# MCU.net
KiCad netlist of a schematic drawn in Altium Designer
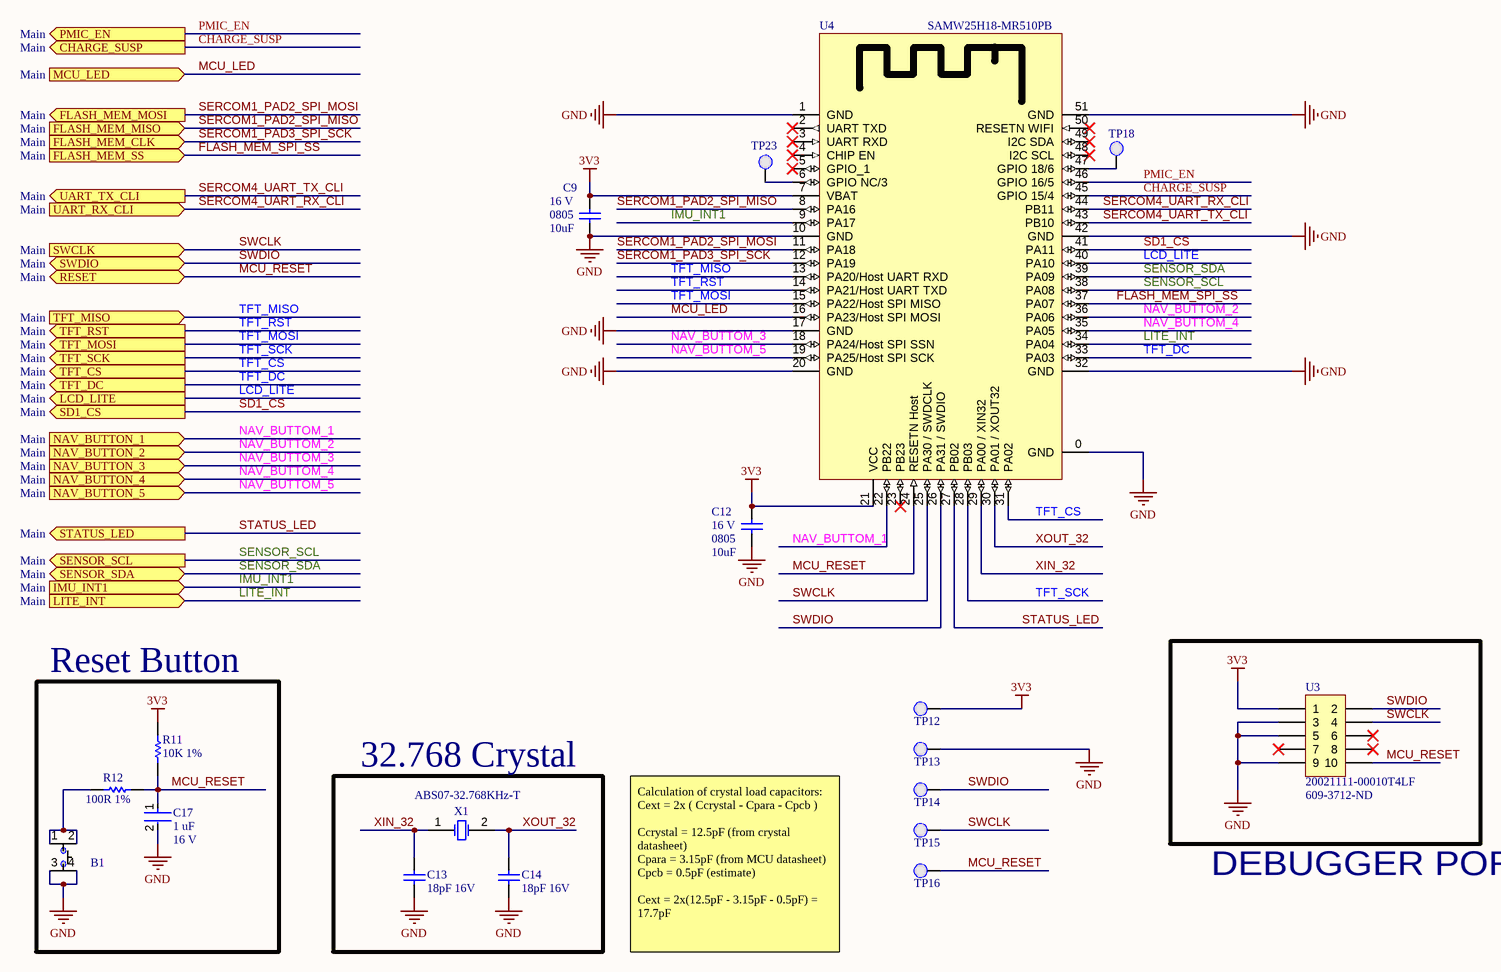
[diagram p0: MCU.SchDoc]

(export (version "E")
  (design (tool "Eeschema 10.0.6"))
  (components
    (comp (ref "B1")
      (value "PTS810 SJK 250 SMTR LFS")
      (footprint "PTS810 SJK 250 SMTR LFS")
      (description "SWITCH TACTILE SPST-NO 0.05A 16V Tactile Switch SPST-NO Top Actuated Surface Mount")
      (fields
        (field (name "MANUFACTURER") "ITT /  C&K Components")
        (field (name "MANUFACTURER PART NUMBER") "PTS810SJK250SMTRLFS")
      )
      (libsource (lib "Schematics") (part "PTS810 SJK 250 SMTR LFS"))
    )
    (comp (ref "C9")
      (value "10uF")
      (footprint "CAPC0805(2012)145_N")
      (description "CAP 10uF 16V ±10% 0805 (2012 Metric) Thickness 1.45mm SMD")
      (fields
        (field (name "RATED VOLTAGE") "16 V")
        (field (name "CASE-EIA") "0805")
        (field (name "TOLERANCE") "Â±10%")
        (field (name "MANUFACTURER PART NUMBER") "CC0805KKX7R7BB106")
      )
      (libsource (lib "ProtoWatch_Compiled") (part "CMP-1036-04927-1"))
    )
    (comp (ref "C12")
      (value "10uF")
      (footprint "CAPC0805(2012)145_N")
      (description "CAP 10uF 16V ±10% 0805 (2012 Metric) Thickness 1.45mm SMD")
      (fields
        (field (name "RATED VOLTAGE") "16 V")
        (field (name "CASE-EIA") "0805")
        (field (name "TOLERANCE") "Â±10%")
        (field (name "MANUFACTURER PART NUMBER") "CC0805KKX7R7BB106")
      )
      (libsource (lib "ProtoWatch_Compiled") (part "CMP-1036-04927-1"))
    )
    (comp (ref "C13")
      (value "18pF 16V")
      (footprint "CAPC0603(1608)100_N")
      (description "CAP 18pF 16V ±5% 0603 (1608 Metric) Thickness 1mm SMD")
      (fields (field (name "TOLERANCE") "Â±5%"))
      (libsource (lib "Altium Content Vault") (part "CAP"))
    )
    (comp (ref "C14")
      (value "18pF 16V")
      (footprint "CAPC0603(1608)100_N")
      (description "CAP 18pF 16V ±5% 0603 (1608 Metric) Thickness 1mm SMD")
      (fields (field (name "TOLERANCE") "Â±5%"))
      (libsource (lib "Altium Content Vault") (part "CAP"))
    )
    (comp (ref "C17")
      (value "1 uF")
      (footprint "FP-CC0603-DA-MFG")
      (description "CAP CER 1UF 16V X7R 0603")
      (fields
        (field (name "TOLERANCE") "0.1")
        (field (name "MANUFACTURER") "YAGEO")
        (field (name "VOLTAGE") "16 V")
      )
      (libsource (lib "Altium Content Vault") (part "11868f565c42a9108669ba33697ecf6"))
    )
    (comp (ref "R11")
      (value "10K 1%")
      (footprint "RESC0603(1608)_N")
      (description "10K 0.1W 1% 0603 (1608 Metric)  SMD")
      (fields (field (name "POWER") "0.1 W") (field (name "TOLERANCE") "1 %"))
      (libsource (lib "Altium Content Vault") (part "RES"))
    )
    (comp (ref "R12")
      (value "100R 1%")
      (footprint "RESC0603(1608)_N")
      (description "100R 0.1W 1% 0603 (1608 Metric)  SMD")
      (fields (field (name "TOLERANCE") "1 %") (field (name "POWER") "0.1 W"))
      (libsource (lib "Altium Content Vault") (part "RES"))
    )
    (comp (ref "TP12")
      (value "0.1\" Pad")
      (footprint "PCBComponent")
      (libsource (lib "Components - 12.02.20 - 18.05") (part "0.1{dblquote} Pad-A.4"))
    )
    (comp (ref "TP13")
      (value "0.1\" Pad")
      (footprint "PCBComponent")
      (libsource (lib "Components - 12.02.20 - 18.05") (part "0.1{dblquote} Pad-A.4"))
    )
    (comp (ref "TP14")
      (value "0.1\" Pad")
      (footprint "PCBComponent")
      (libsource (lib "Components - 12.02.20 - 18.05") (part "0.1{dblquote} Pad-A.4"))
    )
    (comp (ref "TP15")
      (value "0.1\" Pad")
      (footprint "PCBComponent")
      (libsource (lib "Components - 12.02.20 - 18.05") (part "0.1{dblquote} Pad-A.4"))
    )
    (comp (ref "TP16")
      (value "0.1\" Pad")
      (footprint "PCBComponent")
      (libsource (lib "Components - 12.02.20 - 18.05") (part "0.1{dblquote} Pad-A.4"))
    )
    (comp (ref "TP18")
      (value "0.1\" Pad")
      (footprint "PCBComponent")
      (libsource (lib "Components - 12.02.20 - 18.05") (part "0.1{dblquote} Pad-A.4"))
    )
    (comp (ref "TP23")
      (value "0.1\" Pad")
      (footprint "PCBComponent")
      (libsource (lib "Components - 12.02.20 - 18.05") (part "0.1{dblquote} Pad-A.4"))
    )
    (comp (ref "U3")
      (value "20021111-00010T4LF")
      (footprint "20021111-00010T4LF")
      (description "CONN HEADER 10POS UNSHD VERT T/H")
      (fields
        (field (name "MANUFACTURER") "Amphenol / FCI")
        (field (name "SUPPLIER PART NUMBER 1") "609-3712-ND")
      )
      (libsource (lib "Schematics") (part "20021111-00010T4LF"))
    )
    (comp (ref "U4")
      (value "SAMW25H18-MR510PB")
      (footprint "SAMW25H18-MR510PB")
      (description "RF TXRX MODULE WIFI TRACE ANT")
      (fields
        (field (name "MANUFACTURER") "Atmel")
        (field (name "MANUFACTURER PART NUMBER") "ATSAMW25H18-MR510PB")
      )
      (libsource (lib "Schematics") (part "SAMW25H18-MR510PB"))
    )
    (comp (ref "X1")
      (value "ABS07-32.768KHz-T")
      (footprint "ABRA-ABS07-2_V")
      (description "Crystal, 32.768 kHz, 12.5 pF, -40 to 85 degC, SMD Low Profile 3.2 x 1.5 x 0.9 mm, Tape and Reel")
      (fields (field (name "MANUFACTURER") "Abracon"))
      (libsource (lib "Altium Content Vault") (part "ABRA-ABS07-2"))
    )
  )
  (nets
    (net (code "1") (name "/CHARGE_SUSP") (class "Default")
      (node (ref "U4") (pin "45") (pinfunction "GPIO_15/4_45") (pintype "bidirectional"))
    )
    (net (code "2") (name "/FLASH_MEM_SPI_SS") (class "Default")
      (node (ref "U4") (pin "37") (pinfunction "PA07_37") (pintype "bidirectional"))
    )
    (net (code "3") (name "/IMU_INT1") (class "Default")
      (node (ref "U4") (pin "9") (pinfunction "PA17_9") (pintype "bidirectional"))
    )
    (net (code "4") (name "/LCD_LITE") (class "Default")
      (node (ref "U4") (pin "40") (pinfunction "PA10_40") (pintype "bidirectional"))
    )
    (net (code "5") (name "/LITE_INT") (class "Default")
      (node (ref "U4") (pin "34") (pinfunction "PA04_34") (pintype "bidirectional"))
    )
    (net (code "6") (name "/MCU_LED") (class "Default")
      (node (ref "U4") (pin "16") (pinfunction "PA23/Host_SPI_MOSI_16") (pintype "bidirectional"))
    )
    (net (code "7") (name "/MCU_RESET") (class "Default")
      (node (ref "C17") (pin "1") (pinfunction "1_1") (pintype "passive"))
      (node (ref "R11") (pin "1") (pinfunction "1_1") (pintype "passive"))
      (node (ref "R12") (pin "2") (pinfunction "2_2") (pintype "passive"))
      (node (ref "TP16") (pin "1") (pinfunction "PAD_1") (pintype "passive"))
      (node (ref "U3") (pin "10") (pinfunction "10_10") (pintype "passive"))
      (node (ref "U4") (pin "24") (pinfunction "RESETN_Host_24") (pintype "input"))
    )
    (net (code "8") (name "/NAV_BUTTOM_1") (class "Default")
      (node (ref "U4") (pin "22") (pinfunction "PB22_22") (pintype "bidirectional"))
    )
    (net (code "9") (name "/NAV_BUTTOM_2") (class "Default")
      (node (ref "U4") (pin "36") (pinfunction "PA06_36") (pintype "bidirectional"))
    )
    (net (code "10") (name "/NAV_BUTTOM_3") (class "Default")
      (node (ref "U4") (pin "18") (pinfunction "PA24/Host_SPI_SSN_18") (pintype "bidirectional"))
    )
    (net (code "11") (name "/NAV_BUTTOM_4") (class "Default")
      (node (ref "U4") (pin "35") (pinfunction "PA05_35") (pintype "bidirectional"))
    )
    (net (code "12") (name "/NAV_BUTTOM_5") (class "Default")
      (node (ref "U4") (pin "19") (pinfunction "PA25/Host_SPI_SCK_19") (pintype "bidirectional"))
    )
    (net (code "13") (name "/PMIC_EN") (class "Default")
      (node (ref "U4") (pin "46") (pinfunction "GPIO_16/5_46") (pintype "bidirectional"))
    )
    (net (code "14") (name "/SD1_CS") (class "Default")
      (node (ref "U4") (pin "41") (pinfunction "PA11_41") (pintype "bidirectional"))
    )
    (net (code "15") (name "/SENSOR_SCL") (class "Default")
      (node (ref "U4") (pin "38") (pinfunction "PA08_38") (pintype "bidirectional"))
    )
    (net (code "16") (name "/SENSOR_SDA") (class "Default")
      (node (ref "U4") (pin "39") (pinfunction "PA09_39") (pintype "bidirectional"))
    )
    (net (code "17") (name "/SERCOM1_PAD2_SPI_MISO") (class "Default")
      (node (ref "U4") (pin "8") (pinfunction "PA16_8") (pintype "bidirectional"))
    )
    (net (code "18") (name "/SERCOM1_PAD2_SPI_MOSI") (class "Default")
      (node (ref "U4") (pin "11") (pinfunction "PA18_11") (pintype "bidirectional"))
    )
    (net (code "19") (name "/SERCOM1_PAD3_SPI_SCK") (class "Default")
      (node (ref "U4") (pin "12") (pinfunction "PA19_12") (pintype "bidirectional"))
    )
    (net (code "20") (name "/SERCOM4_UART_RX_CLI") (class "Default")
      (node (ref "U4") (pin "44") (pinfunction "PB11_44") (pintype "bidirectional"))
    )
    (net (code "21") (name "/SERCOM4_UART_TX_CLI") (class "Default")
      (node (ref "U4") (pin "43") (pinfunction "PB10_43") (pintype "bidirectional"))
    )
    (net (code "22") (name "/STATUS_LED") (class "Default")
      (node (ref "U4") (pin "27") (pinfunction "PB02_27") (pintype "bidirectional"))
    )
    (net (code "23") (name "/SWCLK") (class "Default")
      (node (ref "TP15") (pin "1") (pinfunction "PAD_1") (pintype "passive"))
      (node (ref "U3") (pin "4") (pinfunction "4_4") (pintype "passive"))
      (node (ref "U4") (pin "25") (pinfunction "PA30_/_SWDCLK_25") (pintype "bidirectional"))
    )
    (net (code "24") (name "/SWDIO") (class "Default")
      (node (ref "TP14") (pin "1") (pinfunction "PAD_1") (pintype "passive"))
      (node (ref "U3") (pin "2") (pinfunction "2_2") (pintype "passive"))
      (node (ref "U4") (pin "26") (pinfunction "PA31_/_SWDIO_26") (pintype "bidirectional"))
    )
    (net (code "25") (name "/TFT_CS") (class "Default")
      (node (ref "U4") (pin "31") (pinfunction "PA02_31") (pintype "bidirectional"))
    )
    (net (code "26") (name "/TFT_DC") (class "Default")
      (node (ref "U4") (pin "33") (pinfunction "PA03_33") (pintype "bidirectional"))
    )
    (net (code "27") (name "/TFT_MISO") (class "Default")
      (node (ref "U4") (pin "13") (pinfunction "PA20/Host_UART_RXD_13") (pintype "bidirectional"))
    )
    (net (code "28") (name "/TFT_MOSI") (class "Default")
      (node (ref "U4") (pin "15") (pinfunction "PA22/Host_SPI_MISO_15") (pintype "bidirectional"))
    )
    (net (code "29") (name "/TFT_RST") (class "Default")
      (node (ref "U4") (pin "14") (pinfunction "PA21/Host_UART_TXD_14") (pintype "bidirectional"))
    )
    (net (code "30") (name "/TFT_SCK") (class "Default")
      (node (ref "U4") (pin "28") (pinfunction "PB03_28") (pintype "bidirectional"))
    )
    (net (code "31") (name "/XIN_32") (class "Default")
      (node (ref "C13") (pin "2") (pinfunction "2_2") (pintype "passive"))
      (node (ref "U4") (pin "29") (pinfunction "PA00_/_XIN32_29") (pintype "bidirectional"))
      (node (ref "X1") (pin "1") (pinfunction "X1_1") (pintype "passive"))
    )
    (net (code "32") (name "/XOUT_32") (class "Default")
      (node (ref "C14") (pin "2") (pinfunction "2_2") (pintype "passive"))
      (node (ref "U4") (pin "30") (pinfunction "PA01_/_XOUT32_30") (pintype "bidirectional"))
      (node (ref "X1") (pin "2") (pinfunction "X2_2") (pintype "passive"))
    )
    (net (code "33") (name "3V3") (class "Default")
      (node (ref "C12") (pin "2") (pinfunction "2_2") (pintype "passive"))
      (node (ref "C9") (pin "2") (pinfunction "2_2") (pintype "passive"))
      (node (ref "R11") (pin "2") (pinfunction "2_2") (pintype "passive"))
      (node (ref "TP12") (pin "1") (pinfunction "PAD_1") (pintype "passive"))
      (node (ref "U3") (pin "1") (pinfunction "1_1") (pintype "passive"))
      (node (ref "U4") (pin "21") (pinfunction "VCC_21") (pintype "power_in"))
      (node (ref "U4") (pin "7") (pinfunction "VBAT_7") (pintype "power_in"))
    )
    (net (code "34") (name "GND") (class "Default")
      (node (ref "B1") (pin "3") (pinfunction "3_3") (pintype "power_in"))
      (node (ref "B1") (pin "4") (pinfunction "4_4") (pintype "power_in"))
      (node (ref "C12") (pin "1") (pinfunction "1_1") (pintype "passive"))
      (node (ref "C13") (pin "1") (pinfunction "1_1") (pintype "passive"))
      (node (ref "C14") (pin "1") (pinfunction "1_1") (pintype "passive"))
      (node (ref "C17") (pin "2") (pinfunction "2_2") (pintype "passive"))
      (node (ref "C9") (pin "1") (pinfunction "1_1") (pintype "passive"))
      (node (ref "TP13") (pin "1") (pinfunction "PAD_1") (pintype "passive"))
      (node (ref "U3") (pin "3") (pinfunction "3_3") (pintype "passive"))
      (node (ref "U3") (pin "5") (pinfunction "5_5") (pintype "passive"))
      (node (ref "U3") (pin "9") (pinfunction "9_9") (pintype "passive"))
      (node (ref "U4") (pin "0") (pinfunction "GND_0") (pintype "power_in"))
      (node (ref "U4") (pin "1") (pinfunction "GND_1") (pintype "power_in"))
      (node (ref "U4") (pin "10") (pinfunction "GND_10") (pintype "power_in"))
      (node (ref "U4") (pin "17") (pinfunction "GND_17") (pintype "power_in"))
      (node (ref "U4") (pin "20") (pinfunction "GND_20") (pintype "power_in"))
      (node (ref "U4") (pin "32") (pinfunction "GND_32") (pintype "power_in"))
      (node (ref "U4") (pin "42") (pinfunction "GND_42") (pintype "power_in"))
      (node (ref "U4") (pin "51") (pinfunction "GND_51") (pintype "power_in"))
    )
    (net (code "35") (name "Net-(B1-Pad1)") (class "Default")
      (node (ref "B1") (pin "1") (pinfunction "1_1") (pintype "power_in"))
      (node (ref "B1") (pin "2") (pinfunction "2_2") (pintype "power_in"))
      (node (ref "R12") (pin "1") (pinfunction "1_1") (pintype "passive"))
    )
    (net (code "36") (name "Net-(TP18-PAD)") (class "Default")
      (node (ref "TP18") (pin "1") (pinfunction "PAD_1") (pintype "passive"))
      (node (ref "U4") (pin "47") (pinfunction "GPIO_18/6_47") (pintype "bidirectional"))
    )
    (net (code "37") (name "Net-(TP23-PAD)") (class "Default")
      (node (ref "TP23") (pin "1") (pinfunction "PAD_1") (pintype "passive"))
      (node (ref "U4") (pin "6") (pinfunction "GPIO_NC/3_6") (pintype "bidirectional"))
    )
    (net (code "38") (name "unconnected-(U3-Pad6)") (class "Default")
      (node (ref "U3") (pin "6") (pinfunction "6_6") (pintype "passive+no_connect"))
    )
    (net (code "39") (name "unconnected-(U3-Pad7)") (class "Default")
      (node (ref "U3") (pin "7") (pinfunction "7_7") (pintype "passive+no_connect"))
    )
    (net (code "40") (name "unconnected-(U3-Pad8)") (class "Default")
      (node (ref "U3") (pin "8") (pinfunction "8_8") (pintype "passive+no_connect"))
    )
    (net (code "41") (name "unconnected-(U4-CHIP_EN-Pad4)") (class "Default")
      (node (ref "U4") (pin "4") (pinfunction "CHIP_EN_4") (pintype "input+no_connect"))
    )
    (net (code "42") (name "unconnected-(U4-GPIO_1-Pad5)") (class "Default")
      (node (ref "U4") (pin "5") (pinfunction "GPIO_1_5") (pintype "bidirectional+no_connect"))
    )
    (net (code "43") (name "unconnected-(U4-I2C_SCL-Pad48)") (class "Default")
      (node (ref "U4") (pin "48") (pinfunction "I2C_SCL_48") (pintype "bidirectional+no_connect"))
    )
    (net (code "44") (name "unconnected-(U4-I2C_SDA-Pad49)") (class "Default")
      (node (ref "U4") (pin "49") (pinfunction "I2C_SDA_49") (pintype "bidirectional+no_connect"))
    )
    (net (code "45") (name "unconnected-(U4-PB23-Pad23)") (class "Default")
      (node (ref "U4") (pin "23") (pinfunction "PB23_23") (pintype "bidirectional+no_connect"))
    )
    (net (code "46") (name "unconnected-(U4-RESETN_WIFI-Pad50)") (class "Default")
      (node (ref "U4") (pin "50") (pinfunction "RESETN_WIFI_50") (pintype "input+no_connect"))
    )
    (net (code "47") (name "unconnected-(U4-UART_RXD-Pad3)") (class "Default")
      (node (ref "U4") (pin "3") (pinfunction "UART_RXD_3") (pintype "input+no_connect"))
    )
    (net (code "48") (name "unconnected-(U4-UART_TXD-Pad2)") (class "Default")
      (node (ref "U4") (pin "2") (pinfunction "UART_TXD_2") (pintype "output+no_connect"))
    )
  )
)
